# pinguino32.net
KiCad netlist of a schematic drawn in EAGLE
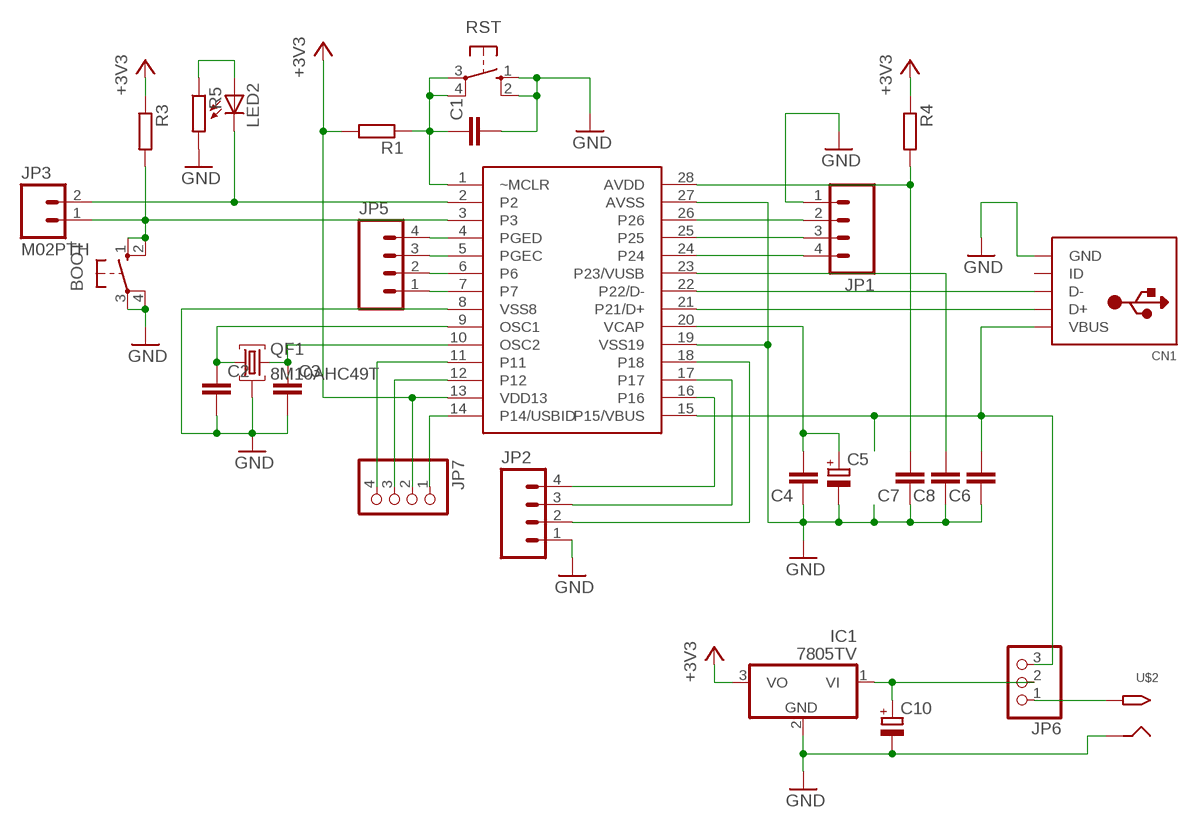
[diagram p0: schematic, sheet 1]

(export (version "E")
  (design (tool "Eeschema 10.0.6"))
  (components
    (comp (ref "BOOT")
      (value "10-XX")
      (footprint "eagle-import:B3F-10XX")
      (libsource (lib "eagle-import") (part "10-XX"))
    )
    (comp (ref "C1")
      (value "C-EU025-025X050")
      (footprint "eagle-import:C025-025X050")
      (libsource (lib "eagle-import") (part "C-EU025-025X050"))
    )
    (comp (ref "C2")
      (value "C-EU025-025X050")
      (footprint "eagle-import:C025-025X050")
      (libsource (lib "eagle-import") (part "C-EU025-025X050"))
    )
    (comp (ref "C3")
      (value "C-EU025-025X050")
      (footprint "eagle-import:C025-025X050")
      (libsource (lib "eagle-import") (part "C-EU025-025X050"))
    )
    (comp (ref "C4")
      (value "C-EU025-025X050")
      (footprint "eagle-import:C025-025X050")
      (libsource (lib "eagle-import") (part "C-EU025-025X050"))
    )
    (comp (ref "C5")
      (value "CPOL-EUE2,5-6E")
      (footprint "eagle-import:E2,5-6E")
      (libsource (lib "eagle-import") (part "CPOL-EUE2,5-6E"))
    )
    (comp (ref "C6")
      (value "C-EU025-025X050")
      (footprint "eagle-import:C025-025X050")
      (libsource (lib "eagle-import") (part "C-EU025-025X050"))
    )
    (comp (ref "C7")
      (value "C-EU025-025X050")
      (footprint "eagle-import:C025-025X050")
      (libsource (lib "eagle-import") (part "C-EU025-025X050"))
    )
    (comp (ref "C8")
      (value "C-EU025-025X050")
      (footprint "eagle-import:C025-025X050")
      (libsource (lib "eagle-import") (part "C-EU025-025X050"))
    )
    (comp (ref "C10")
      (value "CPOL-EUE2,5-6E")
      (footprint "eagle-import:E2,5-6E")
      (libsource (lib "eagle-import") (part "CPOL-EUE2,5-6E"))
    )
    (comp (ref "CN1")
      (value "USBTHM")
      (footprint "eagle-import:USB-MINIB-THM")
      (libsource (lib "eagle-import") (part "USBTHM"))
    )
    (comp (ref "IC1")
      (value "7805TV")
      (footprint "eagle-import:TO220V")
      (libsource (lib "eagle-import") (part "78TV05"))
    )
    (comp (ref "JP1")
      (value "M04PTH")
      (footprint "eagle-import:1X04")
      (libsource (lib "eagle-import") (part "M04PTH"))
    )
    (comp (ref "JP2")
      (value "M04PTH")
      (footprint "eagle-import:1X04")
      (libsource (lib "eagle-import") (part "M04PTH"))
    )
    (comp (ref "JP3")
      (value "M02PTH")
      (footprint "eagle-import:1X02")
      (libsource (lib "eagle-import") (part "M02PTH"))
    )
    (comp (ref "JP5")
      (value "M04PTH")
      (footprint "eagle-import:1X04")
      (libsource (lib "eagle-import") (part "M04PTH"))
    )
    (comp (ref "JP6")
      (value "PINHD-1X3")
      (footprint "eagle-import:1X03")
      (libsource (lib "eagle-import") (part "PINHD-1X3"))
    )
    (comp (ref "JP7")
      (value "PINHD-1X4")
      (footprint "eagle-import:1X04")
      (libsource (lib "eagle-import") (part "PINHD-1X4"))
    )
    (comp (ref "LED2")
      (value "LED3MM")
      (footprint "eagle-import:LED3MM")
      (libsource (lib "eagle-import") (part "LED3MM"))
    )
    (comp (ref "QF1")
      (value "8M10AHC49T")
      (footprint "eagle-import:HC49U")
      (libsource (lib "eagle-import") (part "8M10AHC49T"))
    )
    (comp (ref "R1")
      (value "R-EU_0204/7")
      (footprint "eagle-import:0204_7")
      (libsource (lib "eagle-import") (part "R-EU_0204/7"))
    )
    (comp (ref "R3")
      (value "R-EU_0204/2V")
      (footprint "eagle-import:0204V")
      (libsource (lib "eagle-import") (part "R-EU_0204/2V"))
    )
    (comp (ref "R4")
      (value "R-EU_0204/7")
      (footprint "eagle-import:0204_7")
      (libsource (lib "eagle-import") (part "R-EU_0204/7"))
    )
    (comp (ref "R5")
      (value "R-EU_0204/7")
      (footprint "eagle-import:0204_7")
      (libsource (lib "eagle-import") (part "R-EU_0204/7"))
    )
    (comp (ref "RST")
      (value "10-XX")
      (footprint "eagle-import:B3F-10XX")
      (libsource (lib "eagle-import") (part "10-XX"))
    )
    (comp (ref "U$1")
      (value "PIC32DIP")
      (footprint "eagle-import:SOCKET-28-3")
      (libsource (lib "eagle-import") (part "PIC32DIP"))
    )
    (comp (ref "U$2")
      (value "2.1MMJACKTHM")
      (footprint "eagle-import:PJ-102A")
      (libsource (lib "eagle-import") (part "2.1MMJACKTHM"))
    )
  )
  (nets
    (net (code "1") (name "+3V3") (class "Default")
      (node (ref "IC1") (pin "3") (pinfunction "VO_3") (pintype "passive"))
      (node (ref "JP7") (pin "2") (pinfunction "2_2") (pintype "passive"))
      (node (ref "R1") (pin "2") (pinfunction "2_2") (pintype "passive"))
      (node (ref "R3") (pin "1") (pinfunction "1_1") (pintype "passive"))
      (node (ref "R4") (pin "1") (pinfunction "1_1") (pintype "passive"))
      (node (ref "U$1") (pin "13") (pinfunction "VDD13_13") (pintype "bidirectional"))
    )
    (net (code "2") (name "GND") (class "Default")
      (node (ref "BOOT") (pin "3") (pinfunction "P_3") (pintype "passive"))
      (node (ref "BOOT") (pin "4") (pinfunction "P1_4") (pintype "passive"))
      (node (ref "C1") (pin "2") (pinfunction "2_2") (pintype "passive"))
      (node (ref "C10") (pin "-") (pinfunction "-_-") (pintype "passive"))
      (node (ref "C2") (pin "2") (pinfunction "2_2") (pintype "passive"))
      (node (ref "C3") (pin "2") (pinfunction "2_2") (pintype "passive"))
      (node (ref "C4") (pin "1") (pinfunction "1_1") (pintype "passive"))
      (node (ref "C5") (pin "-") (pinfunction "-_-") (pintype "passive"))
      (node (ref "C6") (pin "1") (pinfunction "1_1") (pintype "passive"))
      (node (ref "C7") (pin "1") (pinfunction "1_1") (pintype "passive"))
      (node (ref "C8") (pin "1") (pinfunction "1_1") (pintype "passive"))
      (node (ref "CN1") (pin "GND") (pinfunction "GND_GND") (pintype "power_in"))
      (node (ref "IC1") (pin "2") (pinfunction "GND_2") (pintype "passive"))
      (node (ref "JP1") (pin "1") (pinfunction "1_1") (pintype "passive"))
      (node (ref "JP2") (pin "1") (pinfunction "1_1") (pintype "passive"))
      (node (ref "QF1") (pin "2") (pinfunction "2_2") (pintype "passive"))
      (node (ref "R5") (pin "2") (pinfunction "2_2") (pintype "passive"))
      (node (ref "RST") (pin "1") (pinfunction "S_1") (pintype "passive"))
      (node (ref "RST") (pin "2") (pinfunction "S1_2") (pintype "passive"))
      (node (ref "U$1") (pin "19") (pinfunction "VSS19_19") (pintype "bidirectional"))
      (node (ref "U$1") (pin "27") (pinfunction "AVSS_27") (pintype "bidirectional"))
      (node (ref "U$1") (pin "8") (pinfunction "VSS8_8") (pintype "bidirectional"))
      (node (ref "U$2") (pin "RING") (pinfunction "RING_RING") (pintype "bidirectional"))
    )
    (net (code "3") (name "Net-(BOOT-S)") (class "Default")
      (node (ref "BOOT") (pin "1") (pinfunction "S_1") (pintype "passive"))
      (node (ref "BOOT") (pin "2") (pinfunction "S1_2") (pintype "passive"))
      (node (ref "JP3") (pin "1") (pinfunction "1_1") (pintype "passive"))
      (node (ref "R3") (pin "2") (pinfunction "2_2") (pintype "passive"))
      (node (ref "U$1") (pin "3") (pinfunction "P3_3") (pintype "bidirectional"))
    )
    (net (code "4") (name "Net-(IC1-VI)") (class "Default")
      (node (ref "C10") (pin "+") (pinfunction "+_+") (pintype "passive"))
      (node (ref "IC1") (pin "1") (pinfunction "VI_1") (pintype "input"))
      (node (ref "JP6") (pin "2") (pinfunction "2_2") (pintype "passive"))
    )
    (net (code "5") (name "Net-(JP6-Pad1)") (class "Default")
      (node (ref "JP6") (pin "1") (pinfunction "1_1") (pintype "passive"))
      (node (ref "U$2") (pin "TIP") (pinfunction "TIP_TIP") (pintype "bidirectional"))
    )
    (net (code "6") (name "Net-(LED2-C)") (class "Default")
      (node (ref "JP3") (pin "2") (pinfunction "2_2") (pintype "passive"))
      (node (ref "LED2") (pin "K") (pinfunction "C_K") (pintype "passive"))
      (node (ref "U$1") (pin "2") (pinfunction "P2_2") (pintype "bidirectional"))
    )
    (net (code "7") (name "Net-(LED2-PadA)") (class "Default")
      (node (ref "LED2") (pin "A") (pinfunction "A_A") (pintype "passive"))
      (node (ref "R5") (pin "1") (pinfunction "1_1") (pintype "passive"))
    )
    (net (code "8") (name "Net-(RST-P)") (class "Default")
      (node (ref "C1") (pin "1") (pinfunction "1_1") (pintype "passive"))
      (node (ref "R1") (pin "1") (pinfunction "1_1") (pintype "passive"))
      (node (ref "RST") (pin "3") (pinfunction "P_3") (pintype "passive"))
      (node (ref "RST") (pin "4") (pinfunction "P1_4") (pintype "passive"))
      (node (ref "U$1") (pin "1") (pinfunction "~{MCLR}_1") (pintype "bidirectional"))
    )
    (net (code "9") (name "Net-(U$1-AVDD)") (class "Default")
      (node (ref "C7") (pin "2") (pinfunction "2_2") (pintype "passive"))
      (node (ref "R4") (pin "2") (pinfunction "2_2") (pintype "passive"))
      (node (ref "U$1") (pin "28") (pinfunction "AVDD_28") (pintype "bidirectional"))
    )
    (net (code "10") (name "Net-(U$1-OSC1)") (class "Default")
      (node (ref "C2") (pin "1") (pinfunction "1_1") (pintype "passive"))
      (node (ref "QF1") (pin "1") (pinfunction "1_1") (pintype "passive"))
      (node (ref "U$1") (pin "9") (pinfunction "OSC1_9") (pintype "bidirectional"))
    )
    (net (code "11") (name "Net-(U$1-OSC2)") (class "Default")
      (node (ref "C3") (pin "1") (pinfunction "1_1") (pintype "passive"))
      (node (ref "QF1") (pin "3") (pinfunction "3_3") (pintype "passive"))
      (node (ref "U$1") (pin "10") (pinfunction "OSC2_10") (pintype "bidirectional"))
    )
    (net (code "12") (name "Net-(U$1-P6)") (class "Default")
      (node (ref "JP5") (pin "2") (pinfunction "2_2") (pintype "passive"))
      (node (ref "U$1") (pin "6") (pinfunction "P6_6") (pintype "bidirectional"))
    )
    (net (code "13") (name "Net-(U$1-P7)") (class "Default")
      (node (ref "JP5") (pin "1") (pinfunction "1_1") (pintype "passive"))
      (node (ref "U$1") (pin "7") (pinfunction "P7_7") (pintype "bidirectional"))
    )
    (net (code "14") (name "Net-(U$1-P11)") (class "Default")
      (node (ref "JP7") (pin "4") (pinfunction "4_4") (pintype "passive"))
      (node (ref "U$1") (pin "11") (pinfunction "P11_11") (pintype "bidirectional"))
    )
    (net (code "15") (name "Net-(U$1-P12)") (class "Default")
      (node (ref "JP7") (pin "3") (pinfunction "3_3") (pintype "passive"))
      (node (ref "U$1") (pin "12") (pinfunction "P12_12") (pintype "bidirectional"))
    )
    (net (code "16") (name "Net-(U$1-P14{slash}USBID)") (class "Default")
      (node (ref "JP7") (pin "1") (pinfunction "1_1") (pintype "passive"))
      (node (ref "U$1") (pin "14") (pinfunction "P14/USBID_14") (pintype "bidirectional"))
    )
    (net (code "17") (name "Net-(U$1-P15{slash}VBUS)") (class "Default")
      (node (ref "C6") (pin "2") (pinfunction "2_2") (pintype "passive"))
      (node (ref "CN1") (pin "VBUS") (pinfunction "VBUS_VBUS") (pintype "power_in"))
      (node (ref "JP6") (pin "3") (pinfunction "3_3") (pintype "passive"))
      (node (ref "U$1") (pin "15") (pinfunction "P15/VBUS_15") (pintype "bidirectional"))
    )
    (net (code "18") (name "Net-(U$1-P16)") (class "Default")
      (node (ref "JP2") (pin "4") (pinfunction "4_4") (pintype "passive"))
      (node (ref "U$1") (pin "16") (pinfunction "P16_16") (pintype "bidirectional"))
    )
    (net (code "19") (name "Net-(U$1-P17)") (class "Default")
      (node (ref "JP2") (pin "3") (pinfunction "3_3") (pintype "passive"))
      (node (ref "U$1") (pin "17") (pinfunction "P17_17") (pintype "bidirectional"))
    )
    (net (code "20") (name "Net-(U$1-P18)") (class "Default")
      (node (ref "JP2") (pin "2") (pinfunction "2_2") (pintype "passive"))
      (node (ref "U$1") (pin "18") (pinfunction "P18_18") (pintype "bidirectional"))
    )
    (net (code "21") (name "Net-(U$1-P21{slash}D+)") (class "Default")
      (node (ref "CN1") (pin "D+") (pinfunction "D+_D+") (pintype "bidirectional"))
      (node (ref "U$1") (pin "21") (pinfunction "P21/D+_21") (pintype "bidirectional"))
    )
    (net (code "22") (name "Net-(U$1-P22{slash}D-)") (class "Default")
      (node (ref "CN1") (pin "D-") (pinfunction "D-_D-") (pintype "bidirectional"))
      (node (ref "U$1") (pin "22") (pinfunction "P22/D-_22") (pintype "bidirectional"))
    )
    (net (code "23") (name "Net-(U$1-P23{slash}VUSB)") (class "Default")
      (node (ref "C8") (pin "2") (pinfunction "2_2") (pintype "passive"))
      (node (ref "U$1") (pin "23") (pinfunction "P23/VUSB_23") (pintype "bidirectional"))
    )
    (net (code "24") (name "Net-(U$1-P24)") (class "Default")
      (node (ref "JP1") (pin "4") (pinfunction "4_4") (pintype "passive"))
      (node (ref "U$1") (pin "24") (pinfunction "P24_24") (pintype "bidirectional"))
    )
    (net (code "25") (name "Net-(U$1-P25)") (class "Default")
      (node (ref "JP1") (pin "3") (pinfunction "3_3") (pintype "passive"))
      (node (ref "U$1") (pin "25") (pinfunction "P25_25") (pintype "bidirectional"))
    )
    (net (code "26") (name "Net-(U$1-P26)") (class "Default")
      (node (ref "JP1") (pin "2") (pinfunction "2_2") (pintype "passive"))
      (node (ref "U$1") (pin "26") (pinfunction "P26_26") (pintype "bidirectional"))
    )
    (net (code "27") (name "Net-(U$1-PGEC)") (class "Default")
      (node (ref "JP5") (pin "3") (pinfunction "3_3") (pintype "passive"))
      (node (ref "U$1") (pin "5") (pinfunction "PGEC_5") (pintype "bidirectional"))
    )
    (net (code "28") (name "Net-(U$1-PGED)") (class "Default")
      (node (ref "JP5") (pin "4") (pinfunction "4_4") (pintype "passive"))
      (node (ref "U$1") (pin "4") (pinfunction "PGED_4") (pintype "bidirectional"))
    )
    (net (code "29") (name "Net-(U$1-VCAP)") (class "Default")
      (node (ref "C4") (pin "2") (pinfunction "2_2") (pintype "passive"))
      (node (ref "C5") (pin "+") (pinfunction "+_+") (pintype "passive"))
      (node (ref "U$1") (pin "20") (pinfunction "VCAP_20") (pintype "bidirectional"))
    )
    (net (code "30") (name "unconnected-(CN1-PadID)") (class "Default")
      (node (ref "CN1") (pin "ID") (pinfunction "ID_ID") (pintype "bidirectional"))
    )
  )
)
